# SWITCH.net
KiCad netlist of a schematic drawn in Altium Designer
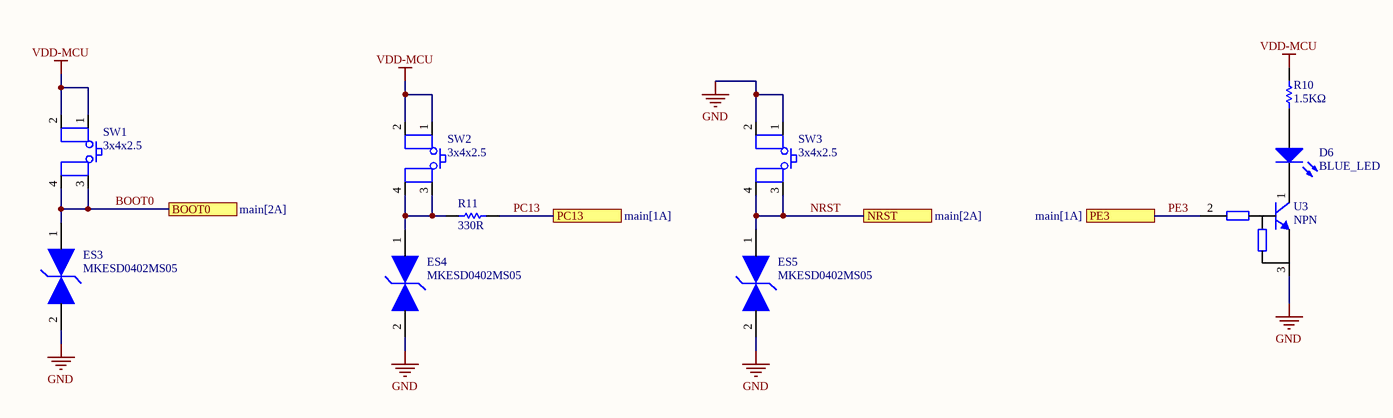
[diagram p0: SWITCH.SchDoc]

(export (version "E")
  (design (tool "Eeschema 10.0.6"))
  (components
    (comp (ref "D6")
      (value "BLUE_LED")
      (footprint "0603_LED_BLUE")
      (description "Typical INFRARED GaAs LED")
      (fields (field (name "PUBLISHER") "Altium Limited"))
      (libsource (lib "Miscellaneous Devices") (part "LED0"))
    )
    (comp (ref "ES3")
      (value "MKESD0402MS05")
      (footprint "MKESD0402MS05")
      (libsource (lib "2226051_이강민_STM32H743") (part "ESD1"))
    )
    (comp (ref "ES4")
      (value "MKESD0402MS05")
      (footprint "MKESD0402MS05")
      (libsource (lib "2226051_이강민_STM32H743") (part "ESD1"))
    )
    (comp (ref "ES5")
      (value "MKESD0402MS05")
      (footprint "MKESD0402MS05")
      (libsource (lib "2226051_이강민_STM32H743") (part "ESD1"))
    )
    (comp (ref "R10")
      (value "1.5KΩ")
      (footprint "0402_Resistor")
      (description "Resistor")
      (fields (field (name "Comment") "Res1") (field (name "PUBLISHER") "Altium Limited"))
      (libsource (lib "Miscellaneous Devices") (part "Res1"))
    )
    (comp (ref "R11")
      (value "330R")
      (footprint "0402_Resistor")
      (description "Resistor")
      (fields (field (name "Comment") "Res1") (field (name "PUBLISHER") "Altium Limited"))
      (libsource (lib "Miscellaneous Devices") (part "Res1"))
    )
    (comp (ref "SW1")
      (value "3x4x2.5")
      (footprint "TACT_switch")
      (libsource (lib "2226051_이강민_STM32H743") (part "SW1"))
    )
    (comp (ref "SW2")
      (value "3x4x2.5")
      (footprint "TACT_switch")
      (libsource (lib "2226051_이강민_STM32H743") (part "SW1"))
    )
    (comp (ref "SW3")
      (value "3x4x2.5")
      (footprint "TACT_switch")
      (libsource (lib "2226051_이강민_STM32H743") (part "SW1"))
    )
    (comp (ref "U3")
      (value "NPN")
      (footprint "SOT23_3L")
      (libsource (lib "2226051_이강민_STM32H743") (part "NPN_REC2"))
    )
  )
  (nets
    (net (code "1") (name "/BOOT0") (class "Default")
      (node (ref "ES3") (pin "1") (pinfunction "1_1") (pintype "passive"))
      (node (ref "SW1") (pin "3") (pinfunction "3_3") (pintype "passive"))
      (node (ref "SW1") (pin "4") (pinfunction "4_4") (pintype "passive"))
    )
    (net (code "2") (name "/NRST") (class "Default")
      (node (ref "ES5") (pin "1") (pinfunction "1_1") (pintype "passive"))
      (node (ref "SW3") (pin "3") (pinfunction "3_3") (pintype "passive"))
      (node (ref "SW3") (pin "4") (pinfunction "4_4") (pintype "passive"))
    )
    (net (code "3") (name "/PC13") (class "Default")
      (node (ref "R11") (pin "1") (pinfunction "1_1") (pintype "passive"))
    )
    (net (code "4") (name "/PE3") (class "Default")
      (node (ref "U3") (pin "2") (pinfunction "2_2") (pintype "passive"))
    )
    (net (code "5") (name "GND") (class "Default")
      (node (ref "ES3") (pin "2") (pinfunction "2_2") (pintype "passive"))
      (node (ref "ES4") (pin "2") (pinfunction "2_2") (pintype "passive"))
      (node (ref "ES5") (pin "2") (pinfunction "2_2") (pintype "passive"))
      (node (ref "SW3") (pin "1") (pinfunction "1_1") (pintype "passive"))
      (node (ref "SW3") (pin "2") (pinfunction "2_2") (pintype "passive"))
      (node (ref "U3") (pin "3") (pinfunction "3_3") (pintype "passive"))
    )
    (net (code "6") (name "Net-(D6-A)") (class "Default")
      (node (ref "D6") (pin "1") (pinfunction "A_1") (pintype "passive"))
      (node (ref "R10") (pin "2") (pinfunction "2_2") (pintype "passive"))
    )
    (net (code "7") (name "Net-(D6-K)") (class "Default")
      (node (ref "D6") (pin "2") (pinfunction "K_2") (pintype "passive"))
      (node (ref "U3") (pin "1") (pinfunction "I_1") (pintype "passive"))
    )
    (net (code "8") (name "Net-(ES4-Pad1)") (class "Default")
      (node (ref "ES4") (pin "1") (pinfunction "1_1") (pintype "passive"))
      (node (ref "R11") (pin "2") (pinfunction "2_2") (pintype "passive"))
      (node (ref "SW2") (pin "3") (pinfunction "3_3") (pintype "passive"))
      (node (ref "SW2") (pin "4") (pinfunction "4_4") (pintype "passive"))
    )
    (net (code "9") (name "VDD-MCU") (class "Default")
      (node (ref "R10") (pin "1") (pinfunction "1_1") (pintype "passive"))
      (node (ref "SW1") (pin "1") (pinfunction "1_1") (pintype "passive"))
      (node (ref "SW1") (pin "2") (pinfunction "2_2") (pintype "passive"))
      (node (ref "SW2") (pin "1") (pinfunction "1_1") (pintype "passive"))
      (node (ref "SW2") (pin "2") (pinfunction "2_2") (pintype "passive"))
    )
  )
)
